# can.net
KiCad netlist of a schematic drawn in Altium Designer
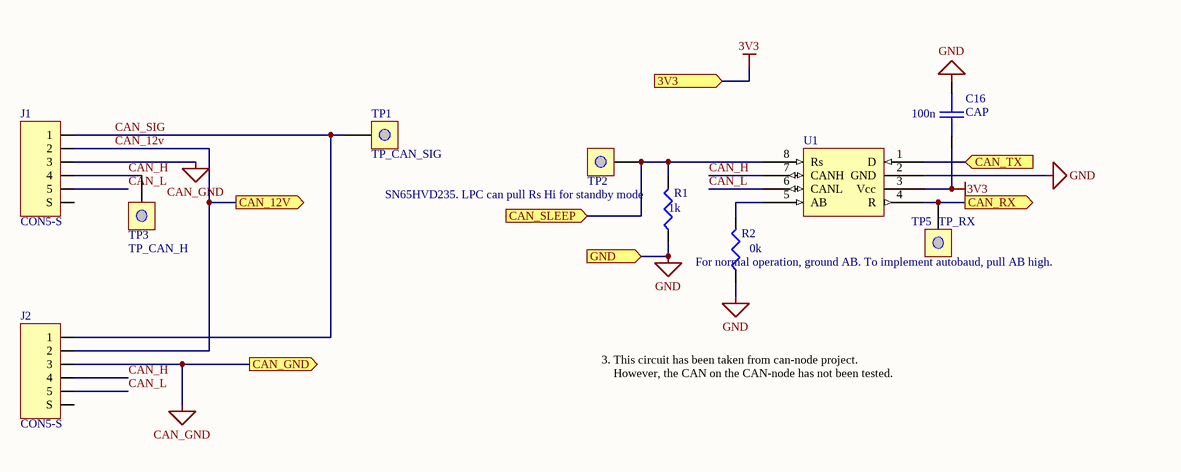
[diagram p0: can.SchDoc]

(export (version "E")
  (design (tool "Eeschema 10.0.6"))
  (components
    (comp (ref "C16")
      (value "CAP")
      (footprint "0603")
      (description "Capacitor")
      (fields (field (name "ALTIUM_VALUE") "100n"))
      (libsource (lib "RCLDQ") (part "CAP"))
    )
    (comp (ref "J1")
      (value "CON5-S")
      (footprint "TRIAD5F")
      (description "Connector, 2 pin, with shield @ S")
      (libsource (lib "Connectors") (part "CON5-S"))
    )
    (comp (ref "J2")
      (value "CON5-S")
      (footprint "TRIAD5F")
      (description "Connector, 2 pin, with shield @ S")
      (libsource (lib "Connectors") (part "CON5-S"))
    )
    (comp (ref "R1")
      (value "1k")
      (footprint "0603")
      (description "Resistor")
      (fields (field (name "Comment") "RES1"))
      (libsource (lib "RCLDQ") (part "RES1"))
    )
    (comp (ref "R2")
      (value "For normal operation, ground AB. To implement autobaud, pull AB high.")
      (footprint "0603")
      (description "Resistor")
      (fields (field (name "ALTIUM_VALUE") "0k"))
      (libsource (lib "RCLDQ") (part "RES1"))
    )
    (comp (ref "TP1")
      (value "TP_CAN_SIG")
      (footprint "TESTPOINT")
      (description "TEST POINT for 12V on CAN")
      (libsource (lib "") (part "TEST_1"))
    )
    (comp (ref "TP2")
      (value "TEST")
      (footprint "TESTPOINT")
      (description "TEST POINT")
      (libsource (lib "") (part "TEST_2"))
    )
    (comp (ref "TP3")
      (value "TP_CAN_H")
      (footprint "TESTPOINT")
      (description "TEST POINT")
      (libsource (lib "Miscellaneous") (part "TEST"))
    )
    (comp (ref "TP5")
      (value "TP_RX")
      (footprint "TESTPOINT")
      (description "TEST POINT")
      (libsource (lib "Miscellaneous") (part "TEST"))
    )
    (comp (ref "U1")
      (value "SN65HVD235. LPC can pull Rs Hi for standby mode")
      (footprint "SO8")
      (description "3.3V CAN XCVR W/STANDBY")
      (libsource (lib "CAN") (part "SN65HVD235"))
    )
  )
  (nets
    (net (code "1") (name "/CAN_12v") (class "Default")
      (node (ref "J1") (pin "2") (pinfunction "2_2") (pintype "bidirectional"))
      (node (ref "J2") (pin "2") (pinfunction "2_2") (pintype "bidirectional"))
    )
    (net (code "2") (name "/CAN_H") (class "Default")
      (node (ref "J1") (pin "4") (pinfunction "4_4") (pintype "bidirectional"))
      (node (ref "J2") (pin "4") (pinfunction "4_4") (pintype "bidirectional"))
      (node (ref "TP3") (pin "0") (pinfunction "TP_0") (pintype "passive"))
      (node (ref "U1") (pin "7") (pinfunction "CANH_7") (pintype "bidirectional"))
    )
    (net (code "3") (name "/CAN_L") (class "Default")
      (node (ref "J1") (pin "5") (pinfunction "5_5") (pintype "bidirectional"))
      (node (ref "J2") (pin "5") (pinfunction "5_5") (pintype "bidirectional"))
      (node (ref "U1") (pin "6") (pinfunction "CANL_6") (pintype "bidirectional"))
    )
    (net (code "4") (name "/CAN_RX") (class "Default")
      (node (ref "TP5") (pin "0") (pinfunction "TP_0") (pintype "passive"))
      (node (ref "U1") (pin "4") (pinfunction "R_4") (pintype "output"))
    )
    (net (code "5") (name "/CAN_SIG") (class "Default")
      (node (ref "J1") (pin "1") (pinfunction "1_1") (pintype "bidirectional"))
      (node (ref "J2") (pin "1") (pinfunction "1_1") (pintype "bidirectional"))
      (node (ref "TP1") (pin "0") (pinfunction "TP_0") (pintype "passive"))
    )
    (net (code "6") (name "/CAN_SLEEP") (class "Default")
      (node (ref "R1") (pin "2") (pinfunction "2_2") (pintype "passive"))
      (node (ref "TP2") (pin "0") (pinfunction "TP_0") (pintype "passive"))
      (node (ref "U1") (pin "8") (pinfunction "Rs_8") (pintype "input"))
    )
    (net (code "7") (name "/CAN_TX") (class "Default")
      (node (ref "U1") (pin "1") (pinfunction "D_1") (pintype "input"))
    )
    (net (code "8") (name "3V3") (class "Default")
      (node (ref "C16") (pin "2") (pinfunction "2_2") (pintype "passive"))
      (node (ref "U1") (pin "3") (pinfunction "Vcc_3") (pintype "power_in"))
    )
    (net (code "9") (name "CAN_GND") (class "Default")
      (node (ref "J1") (pin "3") (pinfunction "3_3") (pintype "bidirectional"))
      (node (ref "J2") (pin "3") (pinfunction "3_3") (pintype "bidirectional"))
    )
    (net (code "10") (name "GND") (class "Default")
      (node (ref "C16") (pin "1") (pinfunction "1_1") (pintype "passive"))
      (node (ref "R1") (pin "1") (pinfunction "1_1") (pintype "passive"))
      (node (ref "R2") (pin "1") (pinfunction "1_1") (pintype "passive"))
      (node (ref "U1") (pin "2") (pinfunction "GND_2") (pintype "power_in"))
    )
    (net (code "11") (name "Net-(U1-AB)") (class "Default")
      (node (ref "R2") (pin "2") (pinfunction "2_2") (pintype "passive"))
      (node (ref "U1") (pin "5") (pinfunction "AB_5") (pintype "input"))
    )
    (net (code "12") (name "unconnected-(J1-S-Pad0)") (class "Default")
      (node (ref "J1") (pin "0") (pinfunction "S_0") (pintype "power_in"))
    )
    (net (code "13") (name "unconnected-(J2-S-Pad0)") (class "Default")
      (node (ref "J2") (pin "0") (pinfunction "S_0") (pintype "power_in"))
    )
  )
)
